# GPS_Schematic.net
KiCad netlist of a schematic drawn in Altium Designer
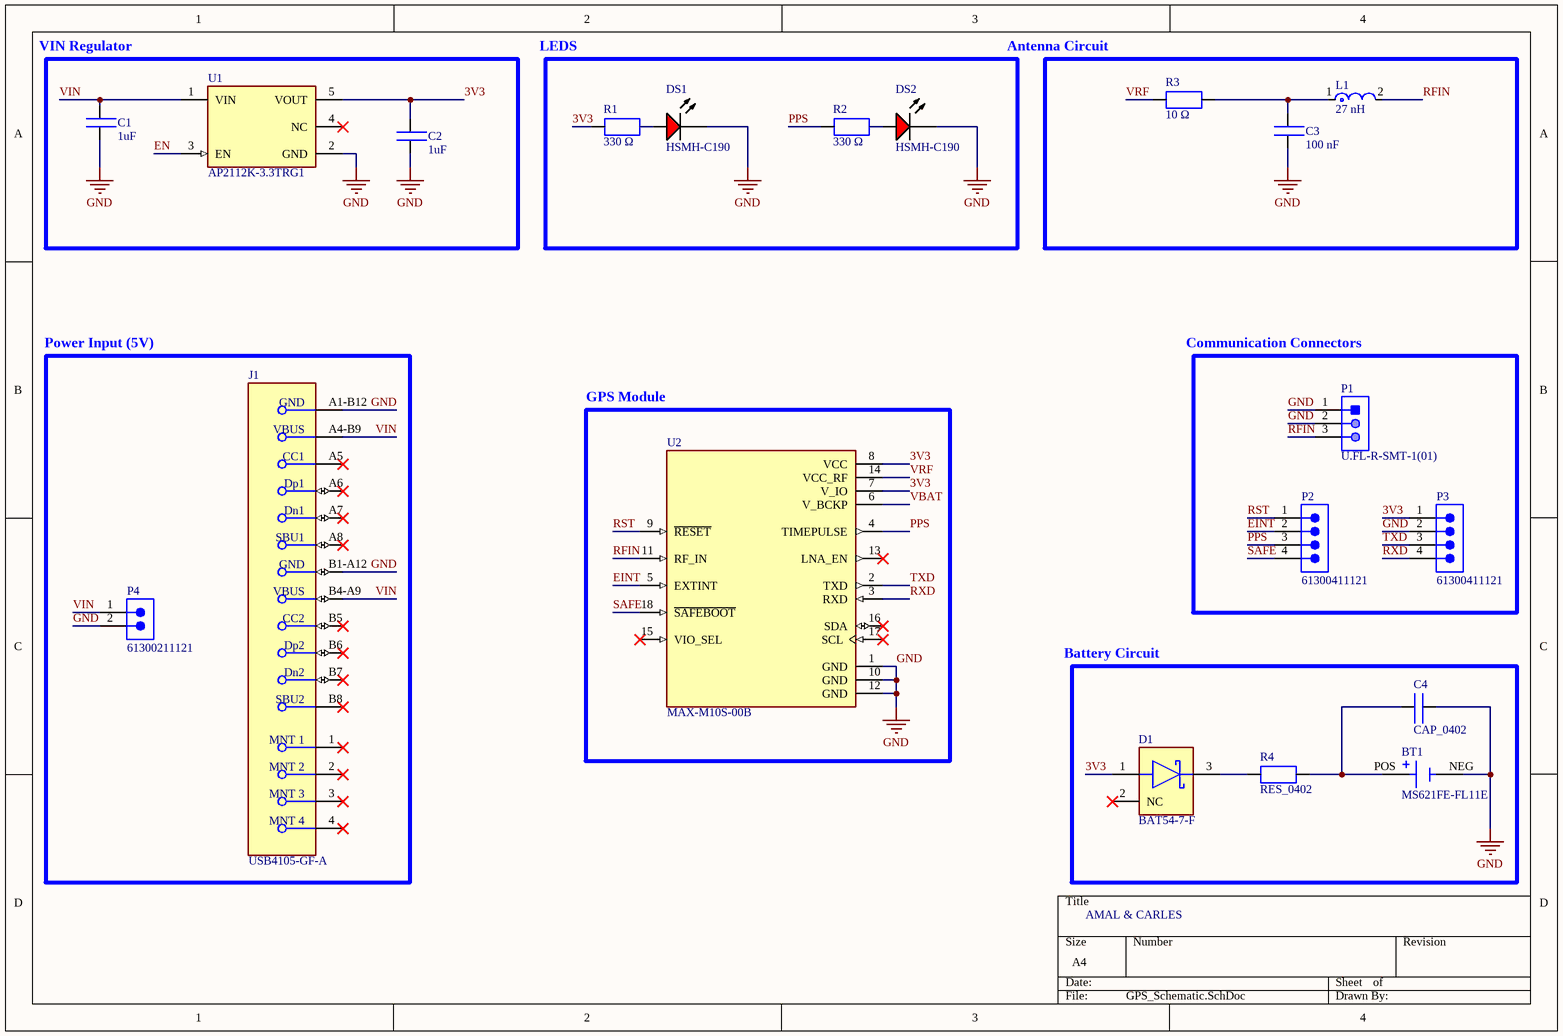
[diagram p0: GPS_Schematic.SchDoc]

(export (version "E")
  (design (tool "Eeschema 10.0.6"))
  (components
    (comp (ref "BT1")
      (value "MS621FE-FL11E")
      (footprint "BAT_MS621FE-FL11E")
      (description "Coin, 6.8mm 3 V Lithium Battery Rechargeable (Secondary) 5.5mAh")
      (fields (field (name "MF") "Seiko Instruments"))
      (libsource (lib "Generic-Schematic-Library") (part "MS621FE-FL11E"))
    )
    (comp (ref "C1")
      (value "1uF")
      (footprint "CAP_0402")
      (description "Capacitor SMD 0402 Generic")
      (fields
        (field (name "MANUFACTURER") "YAGEO")
        (field (name "MANUFACTURER PART NUMBER") "CC0402JRNPO9BN101")
      )
      (libsource (lib "Generic-Schematic-Library") (part "CAP_0402"))
    )
    (comp (ref "C2")
      (value "1uF")
      (footprint "CAP_0402")
      (description "Capacitor SMD 0402 Generic")
      (fields
        (field (name "MANUFACTURER") "YAGEO")
        (field (name "MANUFACTURER PART NUMBER") "CC0402JRNPO9BN101")
      )
      (libsource (lib "Generic-Schematic-Library") (part "CAP_0402"))
    )
    (comp (ref "C3")
      (value "100 nF")
      (footprint "CAP_0402")
      (description "Capacitor SMD 0402 Generic")
      (fields
        (field (name "MANUFACTURER") "YAGEO")
        (field (name "MANUFACTURER PART NUMBER") "CC0402JRNPO9BN101")
      )
      (libsource (lib "Generic-Schematic-Library") (part "CAP_0402"))
    )
    (comp (ref "C4")
      (value "CAP_0402")
      (footprint "CAP_0402")
      (description "Capacitor SMD 0402 Generic")
      (fields
        (field (name "MANUFACTURER") "YAGEO")
        (field (name "MANUFACTURER PART NUMBER") "CC0402JRNPO9BN101")
      )
      (libsource (lib "Generic-Schematic-Library") (part "CAP_0402"))
    )
    (comp (ref "D1")
      (value "BAT54-7-F")
      (footprint "FP-SOT23-IPC_C")
      (description "DIODE SCHOTTKY 30V 200MA SOT23-3")
      (fields
        (field (name "MANUFACTURER") "Diodes Inc.")
        (field (name "OCTOPART") "https://octopart.com/bat54-7-f-diodes+inc.-39681803")
      )
      (libsource (lib "Generic-Schematic-Library") (part "CMP-0303-00002-2"))
    )
    (comp (ref "DS1")
      (value "HSMH-C190")
      (footprint "HSMH-C190")
      (description "LED Uni-Color Red, 65 mW, 20 mA, -40 to 85 degC, 2-Pin SMD, RoHS, Tape and Reel")
      (libsource (lib "Generic-Schematic-Library") (part "HSMH-C190"))
    )
    (comp (ref "DS2")
      (value "HSMH-C190")
      (footprint "HSMH-C190")
      (description "LED Uni-Color Red, 65 mW, 20 mA, -40 to 85 degC, 2-Pin SMD, RoHS, Tape and Reel")
      (libsource (lib "Generic-Schematic-Library") (part "HSMH-C190"))
    )
    (comp (ref "J1")
      (value "USB4105-GF-A")
      (footprint "FP-USB4105-GF-A-MFG")
      (description "CONN RCPT USB2.0 TYPEC 5A")
      (fields
        (field (name "MANUFACTURER") "GCT")
        (field (name "OCTOPART") "https://octopart.com/usb4105-gf-a-gct-106627878")
      )
      (libsource (lib "Generic-Schematic-Library") (part "CMP-245163-000001-1"))
    )
    (comp (ref "L1")
      (value "27 nH")
      (footprint "FP-LQG15HH_02-IPC_B")
      (description "Multilayer type RF Inductor 27nH ±5% 0.67Ω 300mA 0402")
      (fields (field (name "TOLERANCE") "5%"))
      (libsource (lib "Generic-Schematic-Library") (part "CMP-06042-015205-1"))
    )
    (comp (ref "P1")
      (value "U.FL-R-SMT-1(01)")
      (footprint "HRS-U.FL-R-SMT-3_V")
      (description "Ultra Small Coaxial Connector, 6 GHz, -40 to 90 degC, 3-Pin SMD, RoHS, Bulk")
      (fields (field (name "MANUFACTURER") "Hirose Electric"))
      (libsource (lib "Generic-Schematic-Library") (part "CMP-2000-05153-1"))
    )
    (comp (ref "P2")
      (value "61300411121")
      (footprint "61300411121")
      (description "THT Vertical Pin Header WR-PHD, Pitch 2.54 mm, Single Row, 4 pins")
      (libsource (lib "Generic-Schematic-Library") (part "CMP-1502-01064-4"))
    )
    (comp (ref "P3")
      (value "61300411121")
      (footprint "61300411121")
      (description "THT Vertical Pin Header WR-PHD, Pitch 2.54 mm, Single Row, 4 pins")
      (libsource (lib "Generic-Schematic-Library") (part "CMP-1502-01064-4"))
    )
    (comp (ref "P4")
      (value "61300211121")
      (footprint "61300211121")
      (description "THT Vertical Pin Header WR-PHD, Pitch 2.54 mm, Single Row, 2 pins")
      (libsource (lib "Generic-Schematic-Library") (part "CMP-1712-00002-7"))
    )
    (comp (ref "R1")
      (value "330 Ω")
      (footprint "RES_0402")
      (description "Resistor SMD 0402 Generic")
      (fields
        (field (name "MANUFACTURER") "YAGEO")
        (field (name "MANUFACTURER PART NUMBER") "RC0402FR07150KL")
      )
      (libsource (lib "Generic-Schematic-Library") (part "RES_0402"))
    )
    (comp (ref "R2")
      (value "330 Ω")
      (footprint "RES_0402")
      (description "Resistor SMD 0402 Generic")
      (fields
        (field (name "MANUFACTURER") "YAGEO")
        (field (name "MANUFACTURER PART NUMBER") "RC0402FR07150KL")
      )
      (libsource (lib "Generic-Schematic-Library") (part "RES_0402"))
    )
    (comp (ref "R3")
      (value "10 Ω")
      (footprint "RES_0201")
      (description "Resistor SMD 0201 Generic")
      (fields
        (field (name "MANUFACTURER") "YAGEO")
        (field (name "MANUFACTURER PART NUMBER") "RT0201BRD07200RL")
      )
      (libsource (lib "Generic-Schematic-Library") (part "RES_0201"))
    )
    (comp (ref "R4")
      (value "RES_0402")
      (footprint "RES_0402")
      (description "Resistor SMD 0402 Generic")
      (fields
        (field (name "MANUFACTURER") "YAGEO")
        (field (name "MANUFACTURER PART NUMBER") "RC0402FR07150KL")
      )
      (libsource (lib "Generic-Schematic-Library") (part "RES_0402"))
    )
    (comp (ref "U1")
      (value "AP2112K-3.3TRG1")
      (footprint "FP-SOT25-IPC_C")
      (description "IC REG LINEAR 3.3V 600MA SOT25")
      (libsource (lib "Generic-Schematic-Library") (part "CMP-12756-000035-1"))
    )
    (comp (ref "U2")
      (value "MAX-M10S-00B")
      (footprint "XCVR_MAX-M10S-00B")
      (libsource (lib "Generic-Schematic-Library") (part "MAX-M10S-00B"))
    )
  )
  (nets
    (net (code "1") (name "/3V3") (class "Default")
      (node (ref "C2") (pin "2") (pinfunction "2_2") (pintype "passive"))
      (node (ref "D1") (pin "1") (pinfunction "A_1") (pintype "passive"))
      (node (ref "P3") (pin "1") (pinfunction "1_1") (pintype "passive"))
      (node (ref "R1") (pin "1") (pinfunction "1_1") (pintype "passive"))
      (node (ref "U1") (pin "5") (pinfunction "VOUT_5") (pintype "power_in"))
      (node (ref "U2") (pin "7") (pinfunction "V_IO_7") (pintype "power_in"))
      (node (ref "U2") (pin "8") (pinfunction "VCC_8") (pintype "power_in"))
    )
    (net (code "2") (name "/EINT") (class "Default")
      (node (ref "P2") (pin "2") (pinfunction "2_2") (pintype "passive"))
      (node (ref "U2") (pin "5") (pinfunction "EXTINT_5") (pintype "input"))
    )
    (net (code "3") (name "/EN") (class "Default")
      (node (ref "U1") (pin "3") (pinfunction "EN_3") (pintype "input"))
    )
    (net (code "4") (name "/PPS") (class "Default")
      (node (ref "P2") (pin "3") (pinfunction "3_3") (pintype "passive"))
      (node (ref "R2") (pin "1") (pinfunction "1_1") (pintype "passive"))
      (node (ref "U2") (pin "4") (pinfunction "TIMEPULSE_4") (pintype "output"))
    )
    (net (code "5") (name "/RFIN") (class "Default")
      (node (ref "L1") (pin "2") (pinfunction "2_2") (pintype "passive"))
      (node (ref "P1") (pin "3") (pinfunction "3_3") (pintype "passive"))
      (node (ref "U2") (pin "11") (pinfunction "RF_IN_11") (pintype "input"))
    )
    (net (code "6") (name "/RST") (class "Default")
      (node (ref "P2") (pin "1") (pinfunction "1_1") (pintype "passive"))
      (node (ref "U2") (pin "9") (pinfunction "~{RESET}_9") (pintype "input"))
    )
    (net (code "7") (name "/RXD") (class "Default")
      (node (ref "P3") (pin "4") (pinfunction "4_4") (pintype "passive"))
      (node (ref "U2") (pin "3") (pinfunction "RXD_3") (pintype "input"))
    )
    (net (code "8") (name "/SAFE") (class "Default")
      (node (ref "P2") (pin "4") (pinfunction "4_4") (pintype "passive"))
      (node (ref "U2") (pin "18") (pinfunction "~{SAFEBOOT}_18") (pintype "input"))
    )
    (net (code "9") (name "/TXD") (class "Default")
      (node (ref "P3") (pin "3") (pinfunction "3_3") (pintype "passive"))
      (node (ref "U2") (pin "2") (pinfunction "TXD_2") (pintype "output"))
    )
    (net (code "10") (name "/VBAT") (class "Default")
      (node (ref "U2") (pin "6") (pinfunction "V_BCKP_6") (pintype "power_in"))
    )
    (net (code "11") (name "/VIN") (class "Default")
      (node (ref "C1") (pin "2") (pinfunction "2_2") (pintype "passive"))
      (node (ref "J1") (pin "A4-B9") (pinfunction "VBUS_A4-B9") (pintype "power_in"))
      (node (ref "J1") (pin "B4-A9") (pinfunction "VBUS_B4-A9") (pintype "bidirectional"))
      (node (ref "P4") (pin "1") (pinfunction "1_1") (pintype "passive"))
      (node (ref "U1") (pin "1") (pinfunction "VIN_1") (pintype "power_in"))
    )
    (net (code "12") (name "/VRF") (class "Default")
      (node (ref "R3") (pin "1") (pinfunction "1_1") (pintype "passive"))
      (node (ref "U2") (pin "14") (pinfunction "VCC_RF_14") (pintype "power_in"))
    )
    (net (code "13") (name "GND") (class "Default")
      (node (ref "BT1") (pin "NEG") (pinfunction "NEG_NEG") (pintype "passive"))
      (node (ref "C1") (pin "1") (pinfunction "1_1") (pintype "passive"))
      (node (ref "C2") (pin "1") (pinfunction "1_1") (pintype "passive"))
      (node (ref "C3") (pin "1") (pinfunction "1_1") (pintype "passive"))
      (node (ref "C4") (pin "2") (pinfunction "2_2") (pintype "passive"))
      (node (ref "DS1") (pin "2") (pinfunction "K_2") (pintype "passive"))
      (node (ref "DS2") (pin "2") (pinfunction "K_2") (pintype "passive"))
      (node (ref "J1") (pin "A1-B12") (pinfunction "GND_A1-B12") (pintype "power_in"))
      (node (ref "J1") (pin "B1-A12") (pinfunction "GND_B1-A12") (pintype "bidirectional"))
      (node (ref "P1") (pin "1") (pinfunction "1_1") (pintype "passive"))
      (node (ref "P1") (pin "2") (pinfunction "2_2") (pintype "passive"))
      (node (ref "P3") (pin "2") (pinfunction "2_2") (pintype "passive"))
      (node (ref "P4") (pin "2") (pinfunction "2_2") (pintype "passive"))
      (node (ref "U1") (pin "2") (pinfunction "GND_2") (pintype "power_in"))
      (node (ref "U2") (pin "1") (pinfunction "GND_1") (pintype "power_in"))
      (node (ref "U2") (pin "10") (pinfunction "GND_10") (pintype "power_in"))
      (node (ref "U2") (pin "12") (pinfunction "GND_12") (pintype "power_in"))
    )
    (net (code "14") (name "Net-(BT1-PadPOS)") (class "Default")
      (node (ref "BT1") (pin "POS") (pinfunction "POS_POS") (pintype "passive"))
      (node (ref "C4") (pin "1") (pinfunction "1_1") (pintype "passive"))
      (node (ref "R4") (pin "2") (pinfunction "2_2") (pintype "passive"))
    )
    (net (code "15") (name "Net-(C3-Pad2)") (class "Default")
      (node (ref "C3") (pin "2") (pinfunction "2_2") (pintype "passive"))
      (node (ref "L1") (pin "1") (pinfunction "1_1") (pintype "passive"))
      (node (ref "R3") (pin "2") (pinfunction "2_2") (pintype "passive"))
    )
    (net (code "16") (name "Net-(D1-C)") (class "Default")
      (node (ref "D1") (pin "3") (pinfunction "C_3") (pintype "passive"))
      (node (ref "R4") (pin "1") (pinfunction "1_1") (pintype "passive"))
    )
    (net (code "17") (name "Net-(DS1-A)") (class "Default")
      (node (ref "DS1") (pin "1") (pinfunction "A_1") (pintype "passive"))
      (node (ref "R1") (pin "2") (pinfunction "2_2") (pintype "passive"))
    )
    (net (code "18") (name "Net-(DS2-A)") (class "Default")
      (node (ref "DS2") (pin "1") (pinfunction "A_1") (pintype "passive"))
      (node (ref "R2") (pin "2") (pinfunction "2_2") (pintype "passive"))
    )
    (net (code "19") (name "unconnected-(D1-NC-Pad2)") (class "Default")
      (node (ref "D1") (pin "2") (pinfunction "NC_2") (pintype "passive+no_connect"))
    )
    (net (code "20") (name "unconnected-(J1-CC1-PadA5)") (class "Default")
      (node (ref "J1") (pin "A5") (pinfunction "CC1_A5") (pintype "power_in+no_connect"))
    )
    (net (code "21") (name "unconnected-(J1-CC2-PadB5)") (class "Default")
      (node (ref "J1") (pin "B5") (pinfunction "CC2_B5") (pintype "bidirectional+no_connect"))
    )
    (net (code "22") (name "unconnected-(J1-Dn1-PadA7)") (class "Default")
      (node (ref "J1") (pin "A7") (pinfunction "Dn1_A7") (pintype "bidirectional+no_connect"))
    )
    (net (code "23") (name "unconnected-(J1-Dn2-PadB7)") (class "Default")
      (node (ref "J1") (pin "B7") (pinfunction "Dn2_B7") (pintype "bidirectional+no_connect"))
    )
    (net (code "24") (name "unconnected-(J1-Dp1-PadA6)") (class "Default")
      (node (ref "J1") (pin "A6") (pinfunction "Dp1_A6") (pintype "bidirectional+no_connect"))
    )
    (net (code "25") (name "unconnected-(J1-Dp2-PadB6)") (class "Default")
      (node (ref "J1") (pin "B6") (pinfunction "Dp2_B6") (pintype "bidirectional+no_connect"))
    )
    (net (code "26") (name "unconnected-(J1-MNT_1-Pad1)") (class "Default")
      (node (ref "J1") (pin "1") (pinfunction "MNT_1_1") (pintype "power_in+no_connect"))
    )
    (net (code "27") (name "unconnected-(J1-MNT_2-Pad2)") (class "Default")
      (node (ref "J1") (pin "2") (pinfunction "MNT_2_2") (pintype "power_in+no_connect"))
    )
    (net (code "28") (name "unconnected-(J1-MNT_3-Pad3)") (class "Default")
      (node (ref "J1") (pin "3") (pinfunction "MNT_3_3") (pintype "power_in+no_connect"))
    )
    (net (code "29") (name "unconnected-(J1-MNT_4-Pad4)") (class "Default")
      (node (ref "J1") (pin "4") (pinfunction "MNT_4_4") (pintype "power_in+no_connect"))
    )
    (net (code "30") (name "unconnected-(J1-SBU1-PadA8)") (class "Default")
      (node (ref "J1") (pin "A8") (pinfunction "SBU1_A8") (pintype "bidirectional+no_connect"))
    )
    (net (code "31") (name "unconnected-(J1-SBU2-PadB8)") (class "Default")
      (node (ref "J1") (pin "B8") (pinfunction "SBU2_B8") (pintype "power_in+no_connect"))
    )
    (net (code "32") (name "unconnected-(U1-NC-Pad4)") (class "Default")
      (node (ref "U1") (pin "4") (pinfunction "NC_4") (pintype "passive+no_connect"))
    )
    (net (code "33") (name "unconnected-(U2-LNA_EN-Pad13)") (class "Default")
      (node (ref "U2") (pin "13") (pinfunction "LNA_EN_13") (pintype "output+no_connect"))
    )
    (net (code "34") (name "unconnected-(U2-SCL-Pad17)") (class "Default")
      (node (ref "U2") (pin "17") (pinfunction "SCL_17") (pintype "input+no_connect"))
    )
    (net (code "35") (name "unconnected-(U2-SDA-Pad16)") (class "Default")
      (node (ref "U2") (pin "16") (pinfunction "SDA_16") (pintype "bidirectional+no_connect"))
    )
    (net (code "36") (name "unconnected-(U2-VIO_SEL-Pad15)") (class "Default")
      (node (ref "U2") (pin "15") (pinfunction "VIO_SEL_15") (pintype "input+no_connect"))
    )
  )
)
